# ESP.net
KiCad netlist of a schematic drawn in Altium Designer
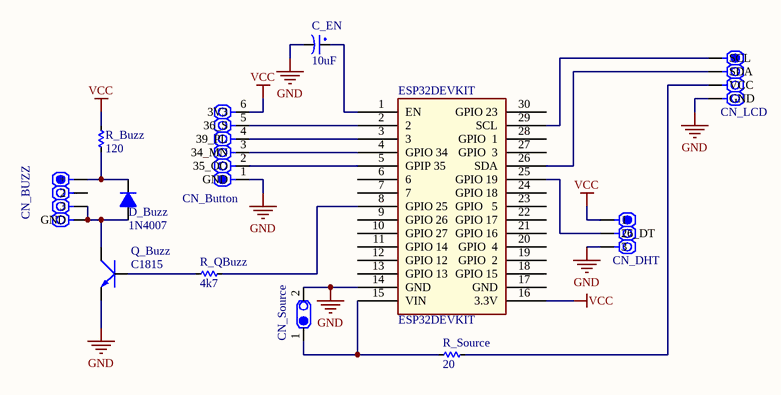
[diagram p0: ESP.SchDoc]

(export (version "E")
  (design (tool "Eeschema 10.0.6"))
  (components
    (comp (ref "CN_Button")
      (value "IO")
      (footprint "CON.HD1X6H")
      (description "Header 1x5")
      (fields (field (name "PUBLISHER") "Hoang Nguyen"))
      (libsource (lib "VPMyLibrary") (part "CON.HDR1x6"))
    )
    (comp (ref "CN_BUZZ")
      (value "IO")
      (footprint "CON.HDR1X4L")
      (description "Header 1x4")
      (fields (field (name "PUBLISHER") "NKIM"))
      (libsource (lib "VPMyLibrary") (part "CON.HDR1x4"))
    )
    (comp (ref "CN_DHT")
      (value "IO")
      (footprint "CON.HDR1X3")
      (description "Header 1x3")
      (fields (field (name "PUBLISHER") "NKIM"))
      (libsource (lib "VPMyLibrary") (part "CON.HDR1x3"))
    )
    (comp (ref "CN_LCD")
      (value "IO")
      (footprint "CON.HDR1X4L")
      (description "Header 1x4")
      (fields (field (name "PUBLISHER") "NKIM"))
      (libsource (lib "VPMyLibrary") (part "CON.HDR1x4"))
    )
    (comp (ref "CN_Source")
      (value "IO")
      (footprint "CON.HDR1X2A")
      (description "Header 1x2")
      (fields (field (name "PUBLISHER") "Hoang Nguyen"))
      (libsource (lib "VPMyLibrary") (part "CON.HDR1x2"))
    )
    (comp (ref "C_EN")
      (value "10uF")
      (footprint "CP1/2")
      (description "Cap P  0,1uF < 22uF , 16 - 50V")
      (libsource (lib "syhaunguyenUPDATED") (part "CP1"))
    )
    (comp (ref "D_Buzz")
      (value "1N4007")
      (footprint "D1A")
      (description "Diode 1A")
      (libsource (lib "syhaunguyenUPDATED") (part "D1A"))
    )
    (comp (ref "ESP32DEVKIT")
      (value "ESP32DEVKIT")
      (footprint "ESP32devKitV1")
      (libsource (lib "ESP32-DEVKIT") (part "ESP32DEVKIT"))
    )
    (comp (ref "Q_Buzz")
      (value "C1815")
      (footprint "QTO-92")
      (description "NPN 600mW, ECB")
      (libsource (lib "syhaunguyenUPDATED") (part "C1815"))
    )
    (comp (ref "R_Buzz")
      (value "120")
      (footprint "RES-1/4W")
      (description "Res")
      (fields
        (field (name "MANUFACTURER") "Generic Components")
        (field (name "PUBLISHER") "Altium Hobart Technology Centre")
      )
      (libsource (lib "LIBRARY") (part "Res"))
    )
    (comp (ref "R_QBuzz")
      (value "4k7")
      (footprint "RES-1/4W")
      (description "Res")
      (fields
        (field (name "MANUFACTURER") "Generic Components")
        (field (name "PUBLISHER") "Altium Hobart Technology Centre")
      )
      (libsource (lib "LIBRARY") (part "Res"))
    )
    (comp (ref "R_Source")
      (value "20")
      (footprint "RES-1/4W")
      (description "Res")
      (fields
        (field (name "MANUFACTURER") "Generic Components")
        (field (name "PUBLISHER") "Altium Hobart Technology Centre")
      )
      (libsource (lib "LIBRARY") (part "Res"))
    )
  )
  (nets
    (net (code "1") (name "GND") (class "Default")
      (node (ref "CN_Button") (pin "1") (pinfunction "GND_1") (pintype "passive"))
      (node (ref "CN_DHT") (pin "3") (pinfunction "3_3") (pintype "passive"))
      (node (ref "CN_LCD") (pin "4") (pinfunction "GND_4") (pintype "passive"))
      (node (ref "CN_Source") (pin "2") (pinfunction "2_2") (pintype "passive"))
      (node (ref "C_EN") (pin "2") (pinfunction "2_2") (pintype "passive"))
      (node (ref "ESP32DEVKIT") (pin "14") (pinfunction "GND_14") (pintype "passive"))
      (node (ref "Q_Buzz") (pin "1") (pinfunction "E_1") (pintype "passive"))
    )
    (net (code "2") (name "Net-(CN_BUZZ-+)") (class "Default")
      (node (ref "CN_BUZZ") (pin "1") (pinfunction "+_1") (pintype "passive"))
      (node (ref "D_Buzz") (pin "2") (pinfunction "K_2") (pintype "passive"))
      (node (ref "R_Buzz") (pin "2") (pinfunction "2_2") (pintype "passive"))
    )
    (net (code "3") (name "Net-(CN_BUZZ-GND)") (class "Default")
      (node (ref "CN_BUZZ") (pin "3") (pinfunction "3_3") (pintype "passive"))
      (node (ref "CN_BUZZ") (pin "4") (pinfunction "GND_4") (pintype "passive"))
      (node (ref "D_Buzz") (pin "1") (pinfunction "A_1") (pintype "passive"))
      (node (ref "Q_Buzz") (pin "2") (pinfunction "C_2") (pintype "passive"))
    )
    (net (code "4") (name "Net-(CN_Button-34_MN)") (class "Default")
      (node (ref "CN_Button") (pin "3") (pinfunction "34_MN_3") (pintype "passive"))
      (node (ref "ESP32DEVKIT") (pin "4") (pinfunction "GPIO_34_4") (pintype "passive"))
    )
    (net (code "5") (name "Net-(CN_Button-35_OO)") (class "Default")
      (node (ref "CN_Button") (pin "2") (pinfunction "35_OO_2") (pintype "passive"))
      (node (ref "ESP32DEVKIT") (pin "5") (pinfunction "GPIP_35_5") (pintype "passive"))
    )
    (net (code "6") (name "Net-(CN_Button-36_S)") (class "Default")
      (node (ref "CN_Button") (pin "5") (pinfunction "36_S_5") (pintype "passive"))
      (node (ref "ESP32DEVKIT") (pin "2") (pinfunction "2_2") (pintype "passive"))
    )
    (net (code "7") (name "Net-(CN_Button-39_PL)") (class "Default")
      (node (ref "CN_Button") (pin "4") (pinfunction "39_PL_4") (pintype "passive"))
      (node (ref "ESP32DEVKIT") (pin "3") (pinfunction "3_3") (pintype "passive"))
    )
    (net (code "8") (name "Net-(CN_DHT-26_DT)") (class "Default")
      (node (ref "CN_DHT") (pin "2") (pinfunction "26_DT_2") (pintype "passive"))
      (node (ref "ESP32DEVKIT") (pin "25") (pinfunction "GPIO_19_25") (pintype "passive"))
    )
    (net (code "9") (name "Net-(CN_LCD-+)") (class "Default")
      (node (ref "CN_LCD") (pin "1") (pinfunction "+_1") (pintype "passive"))
      (node (ref "ESP32DEVKIT") (pin "29") (pinfunction "SCL_29") (pintype "passive"))
    )
    (net (code "10") (name "Net-(CN_LCD-Pad3)") (class "Default")
      (node (ref "CN_LCD") (pin "3") (pinfunction "3_3") (pintype "passive"))
      (node (ref "R_Source") (pin "1") (pinfunction "1_1") (pintype "passive"))
    )
    (net (code "11") (name "Net-(ESP32DEVKIT-EN)") (class "Default")
      (node (ref "C_EN") (pin "1") (pinfunction "1_1") (pintype "passive"))
      (node (ref "ESP32DEVKIT") (pin "1") (pinfunction "EN_1") (pintype "passive"))
    )
    (net (code "12") (name "Net-(ESP32DEVKIT-GPIO_25)") (class "Default")
      (node (ref "ESP32DEVKIT") (pin "8") (pinfunction "GPIO_25_8") (pintype "passive"))
      (node (ref "R_QBuzz") (pin "1") (pinfunction "1_1") (pintype "passive"))
    )
    (net (code "13") (name "Net-(ESP32DEVKIT-SDA)") (class "Default")
      (node (ref "CN_LCD") (pin "2") (pinfunction "2_2") (pintype "passive"))
      (node (ref "ESP32DEVKIT") (pin "26") (pinfunction "SDA_26") (pintype "passive"))
    )
    (net (code "14") (name "Net-(ESP32DEVKIT-VIN)") (class "Default")
      (node (ref "CN_Source") (pin "1") (pinfunction "1_1") (pintype "passive"))
      (node (ref "ESP32DEVKIT") (pin "15") (pinfunction "VIN_15") (pintype "passive"))
      (node (ref "R_Source") (pin "2") (pinfunction "2_2") (pintype "passive"))
    )
    (net (code "15") (name "Net-(Q_Buzz-B)") (class "Default")
      (node (ref "Q_Buzz") (pin "3") (pinfunction "B_3") (pintype "passive"))
      (node (ref "R_QBuzz") (pin "2") (pinfunction "2_2") (pintype "passive"))
    )
    (net (code "16") (name "VCC") (class "Default")
      (node (ref "CN_Button") (pin "6") (pinfunction "3V3_6") (pintype "passive"))
      (node (ref "CN_DHT") (pin "1") (pinfunction "1_1") (pintype "passive"))
      (node (ref "ESP32DEVKIT") (pin "16") (pinfunction "3.3V_16") (pintype "passive"))
      (node (ref "R_Buzz") (pin "1") (pinfunction "1_1") (pintype "passive"))
    )
    (net (code "17") (name "unconnected-(CN_BUZZ-Pad2)") (class "Default")
      (node (ref "CN_BUZZ") (pin "2") (pinfunction "2_2") (pintype "passive"))
    )
    (net (code "18") (name "unconnected-(ESP32DEVKIT-GND-Pad17)") (class "Default")
      (node (ref "ESP32DEVKIT") (pin "17") (pinfunction "GND_17") (pintype "passive"))
    )
    (net (code "19") (name "unconnected-(ESP32DEVKIT-GPIO_12-Pad12)") (class "Default")
      (node (ref "ESP32DEVKIT") (pin "12") (pinfunction "GPIO_12_12") (pintype "passive"))
    )
    (net (code "20") (name "unconnected-(ESP32DEVKIT-GPIO_13-Pad13)") (class "Default")
      (node (ref "ESP32DEVKIT") (pin "13") (pinfunction "GPIO_13_13") (pintype "passive"))
    )
    (net (code "21") (name "unconnected-(ESP32DEVKIT-GPIO_14-Pad11)") (class "Default")
      (node (ref "ESP32DEVKIT") (pin "11") (pinfunction "GPIO_14_11") (pintype "passive"))
    )
    (net (code "22") (name "unconnected-(ESP32DEVKIT-GPIO_15-Pad18)") (class "Default")
      (node (ref "ESP32DEVKIT") (pin "18") (pinfunction "GPIO_15_18") (pintype "passive"))
    )
    (net (code "23") (name "unconnected-(ESP32DEVKIT-GPIO_16-Pad21)") (class "Default")
      (node (ref "ESP32DEVKIT") (pin "21") (pinfunction "GPIO_16_21") (pintype "passive"))
    )
    (net (code "24") (name "unconnected-(ESP32DEVKIT-GPIO_17-Pad22)") (class "Default")
      (node (ref "ESP32DEVKIT") (pin "22") (pinfunction "GPIO_17_22") (pintype "passive"))
    )
    (net (code "25") (name "unconnected-(ESP32DEVKIT-GPIO_18-Pad24)") (class "Default")
      (node (ref "ESP32DEVKIT") (pin "24") (pinfunction "GPIO_18_24") (pintype "passive"))
    )
    (net (code "26") (name "unconnected-(ESP32DEVKIT-GPIO_23-Pad30)") (class "Default")
      (node (ref "ESP32DEVKIT") (pin "30") (pinfunction "GPIO_23_30") (pintype "passive"))
    )
    (net (code "27") (name "unconnected-(ESP32DEVKIT-GPIO_26-Pad9)") (class "Default")
      (node (ref "ESP32DEVKIT") (pin "9") (pinfunction "GPIO_26_9") (pintype "passive"))
    )
    (net (code "28") (name "unconnected-(ESP32DEVKIT-GPIO_27-Pad10)") (class "Default")
      (node (ref "ESP32DEVKIT") (pin "10") (pinfunction "GPIO_27_10") (pintype "passive"))
    )
    (net (code "29") (name "unconnected-(ESP32DEVKIT-GPIO__1-Pad28)") (class "Default")
      (node (ref "ESP32DEVKIT") (pin "28") (pinfunction "GPIO__1_28") (pintype "passive"))
    )
    (net (code "30") (name "unconnected-(ESP32DEVKIT-GPIO__2-Pad19)") (class "Default")
      (node (ref "ESP32DEVKIT") (pin "19") (pinfunction "GPIO__2_19") (pintype "passive"))
    )
    (net (code "31") (name "unconnected-(ESP32DEVKIT-GPIO__3-Pad27)") (class "Default")
      (node (ref "ESP32DEVKIT") (pin "27") (pinfunction "GPIO__3_27") (pintype "passive"))
    )
    (net (code "32") (name "unconnected-(ESP32DEVKIT-GPIO__4-Pad20)") (class "Default")
      (node (ref "ESP32DEVKIT") (pin "20") (pinfunction "GPIO__4_20") (pintype "passive"))
    )
    (net (code "33") (name "unconnected-(ESP32DEVKIT-GPIO___5-Pad23)") (class "Default")
      (node (ref "ESP32DEVKIT") (pin "23") (pinfunction "GPIO___5_23") (pintype "passive"))
    )
    (net (code "34") (name "unconnected-(ESP32DEVKIT-Pad6)") (class "Default")
      (node (ref "ESP32DEVKIT") (pin "6") (pinfunction "6_6") (pintype "passive"))
    )
    (net (code "35") (name "unconnected-(ESP32DEVKIT-Pad7)") (class "Default")
      (node (ref "ESP32DEVKIT") (pin "7") (pinfunction "7_7") (pintype "passive"))
    )
  )
)
